# Adafruit_Trellis_4x4_3mm_HT16K33.net
KiCad netlist of a schematic drawn in Altium Designer
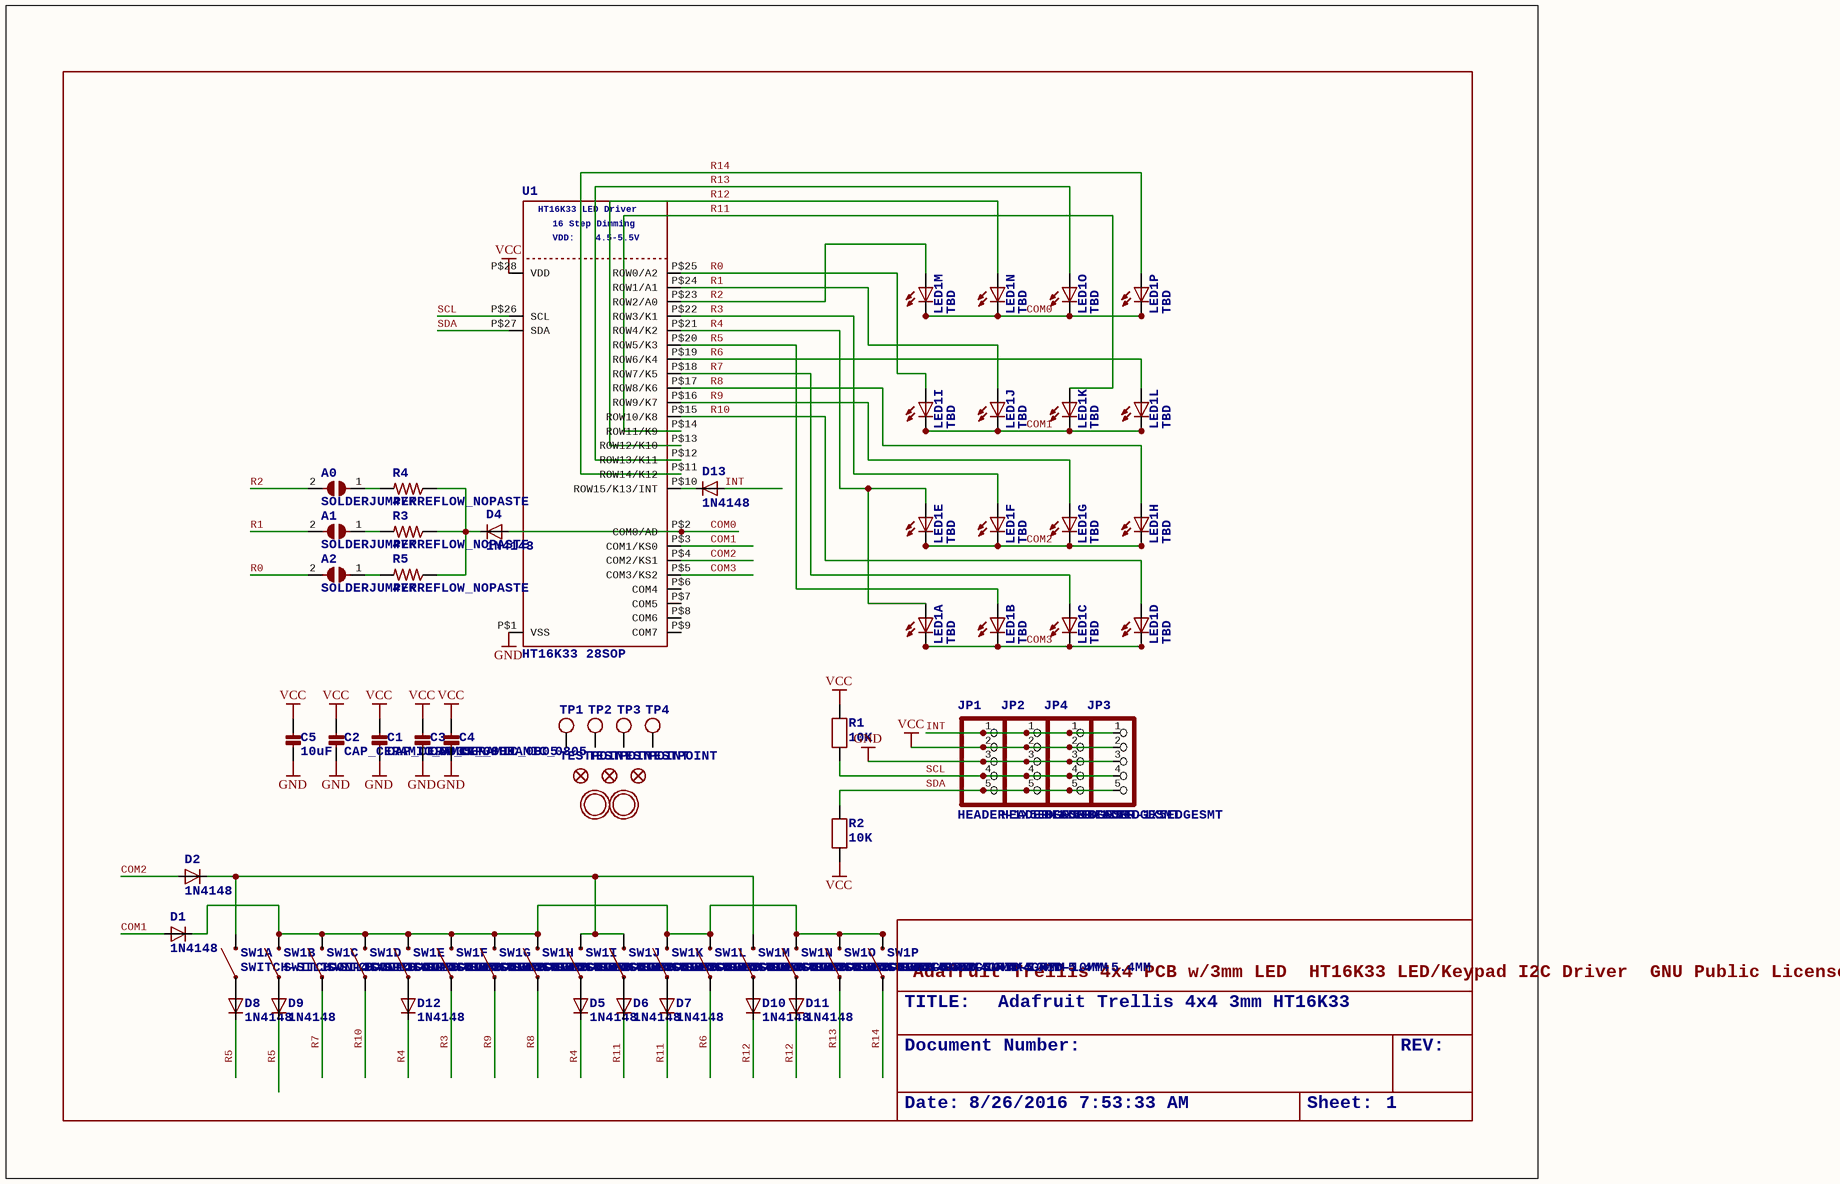
[diagram p0: Adafruit Trellis 4x4 3mm HT16K33.SchDoc]

(export (version "E")
  (design (tool "Eeschema 10.0.6"))
  (components
    (comp (ref "A0")
      (value "SOLDERJUMPERREFLOW_NOPASTE")
      (footprint "SOLDERJUMPER_REFLOW_NOPASTE")
      (libsource (lib "microbuilder") (part "SOLDERJUMPERREFLOW_NOPASTE"))
    )
    (comp (ref "A1")
      (value "SOLDERJUMPERREFLOW_NOPASTE")
      (footprint "SOLDERJUMPER_REFLOW_NOPASTE")
      (libsource (lib "microbuilder") (part "SOLDERJUMPERREFLOW_NOPASTE"))
    )
    (comp (ref "A2")
      (value "SOLDERJUMPERREFLOW_NOPASTE")
      (footprint "SOLDERJUMPER_REFLOW_NOPASTE")
      (libsource (lib "microbuilder") (part "SOLDERJUMPERREFLOW_NOPASTE"))
    )
    (comp (ref "C1")
      (value "CAP_CERAMIC_0805")
      (footprint "_0805")
      (libsource (lib "microbuilder") (part "CAP_CERAMIC_0805"))
    )
    (comp (ref "C2")
      (value "CAP_CERAMIC_0805")
      (footprint "_0805")
      (libsource (lib "microbuilder") (part "CAP_CERAMIC_0805"))
    )
    (comp (ref "C3")
      (value "CAP_CERAMIC_0805")
      (footprint "_0805")
      (libsource (lib "microbuilder") (part "CAP_CERAMIC_0805"))
    )
    (comp (ref "C4")
      (value "CAP_CERAMIC_0805")
      (footprint "_0805")
      (libsource (lib "microbuilder") (part "CAP_CERAMIC_0805"))
    )
    (comp (ref "C5")
      (value "10uF")
      (footprint "_0805")
      (libsource (lib "microbuilder") (part "CAP_CERAMIC_0805"))
    )
    (comp (ref "D1")
      (value "1N4148")
      (footprint "SOD-323")
      (libsource (lib "microbuilder") (part "DIODESOD-323"))
    )
    (comp (ref "D2")
      (value "1N4148")
      (footprint "SOD-323")
      (libsource (lib "microbuilder") (part "DIODESOD-323"))
    )
    (comp (ref "D4")
      (value "1N4148")
      (footprint "SOD-323F")
      (libsource (lib "adafruit") (part "DIODESOD-323F"))
    )
    (comp (ref "D5")
      (value "1N4148")
      (footprint "SOD-323")
      (libsource (lib "microbuilder") (part "DIODESOD-323"))
    )
    (comp (ref "D6")
      (value "1N4148")
      (footprint "SOD-323")
      (libsource (lib "microbuilder") (part "DIODESOD-323"))
    )
    (comp (ref "D7")
      (value "1N4148")
      (footprint "SOD-323")
      (libsource (lib "microbuilder") (part "DIODESOD-323"))
    )
    (comp (ref "D8")
      (value "1N4148")
      (footprint "SOD-323")
      (libsource (lib "microbuilder") (part "DIODESOD-323"))
    )
    (comp (ref "D9")
      (value "1N4148")
      (footprint "SOD-323")
      (libsource (lib "microbuilder") (part "DIODESOD-323"))
    )
    (comp (ref "D10")
      (value "1N4148")
      (footprint "SOD-323")
      (libsource (lib "microbuilder") (part "DIODESOD-323"))
    )
    (comp (ref "D11")
      (value "1N4148")
      (footprint "SOD-323")
      (libsource (lib "microbuilder") (part "DIODESOD-323"))
    )
    (comp (ref "D12")
      (value "1N4148")
      (footprint "SOD-323")
      (libsource (lib "microbuilder") (part "DIODESOD-323"))
    )
    (comp (ref "D13")
      (value "1N4148")
      (footprint "SOD-323")
      (libsource (lib "microbuilder") (part "DIODESOD-323"))
    )
    (comp (ref "FID1")
      (value "FIDUCIAL\"\"")
      (footprint "FIDUCIAL_1MM")
      (description "Fiducial Alignment Points   Various fiducial points for machine vision alignment.")
      (libsource (lib "microbuilder") (part "FIDUCIAL{dblquote}{dblquote}"))
    )
    (comp (ref "FID2")
      (value "FIDUCIAL\"\"")
      (footprint "FIDUCIAL_1MM")
      (description "Fiducial Alignment Points   Various fiducial points for machine vision alignment.")
      (libsource (lib "microbuilder") (part "FIDUCIAL{dblquote}{dblquote}"))
    )
    (comp (ref "FID3")
      (value "FIDUCIAL\"\"")
      (footprint "FIDUCIAL_1MM")
      (description "Fiducial Alignment Points   Various fiducial points for machine vision alignment.")
      (libsource (lib "microbuilder") (part "FIDUCIAL{dblquote}{dblquote}"))
    )
    (comp (ref "JP1")
      (value "HEADER-1X5EDGESMT")
      (footprint "1X5_SMT")
      (description "PIN HEADER")
      (libsource (lib "microbuilder") (part "HEADER-1X5EDGESMT"))
    )
    (comp (ref "JP2")
      (value "HEADER-1X5EDGESMT")
      (footprint "1X5_SMT")
      (description "PIN HEADER")
      (libsource (lib "microbuilder") (part "HEADER-1X5EDGESMT"))
    )
    (comp (ref "JP3")
      (value "HEADER-1X5EDGESMT")
      (footprint "1X5_SMT")
      (description "PIN HEADER")
      (libsource (lib "microbuilder") (part "HEADER-1X5EDGESMT"))
    )
    (comp (ref "JP4")
      (value "HEADER-1X5EDGESMT")
      (footprint "1X5_SMT")
      (description "PIN HEADER")
      (libsource (lib "microbuilder") (part "HEADER-1X5EDGESMT"))
    )
    (comp (ref "LED1")
      (value "TBD")
      (footprint "LED3MM-4X4GRID")
      (libsource (lib "microbuilder") (part "LED-3MM-4X4GRID-3MM"))
    )
    (comp (ref "R1")
      (value "10K")
      (footprint "_0805")
      (libsource (lib "microbuilder") (part "RESISTOR_0805"))
    )
    (comp (ref "R2")
      (value "10K")
      (footprint "_0805")
      (libsource (lib "microbuilder") (part "RESISTOR_0805"))
    )
    (comp (ref "R3")
      (value "47K")
      (footprint "R0805")
      (description "RESISTOR, American symbol")
      (libsource (lib "rcl") (part "R-US_R0805"))
    )
    (comp (ref "R4")
      (value "47K")
      (footprint "R0805")
      (description "RESISTOR, American symbol")
      (libsource (lib "rcl") (part "R-US_R0805"))
    )
    (comp (ref "R5")
      (value "47K")
      (footprint "R0805")
      (description "RESISTOR, American symbol")
      (libsource (lib "rcl") (part "R-US_R0805"))
    )
    (comp (ref "SW1")
      (value "SWITCH-SILICON-4X4GRID-10MM-5.4MM")
      (footprint "ELAST_PAD_SQUARE_10MM_5.4MM_4X4GRID")
      (libsource (lib "") (part "SWITCH-SILICON-4X4GRID-10MM-5.4MM_7"))
    )
    (comp (ref "TP1")
      (value "TESTPOINT")
      (footprint "TESTPOINT_SMT")
      (libsource (lib "microbuilder") (part "TESTPOINT"))
    )
    (comp (ref "TP2")
      (value "TESTPOINT")
      (footprint "TESTPOINT_SMT")
      (libsource (lib "microbuilder") (part "TESTPOINT"))
    )
    (comp (ref "TP3")
      (value "TESTPOINT")
      (footprint "TESTPOINT_SMT")
      (libsource (lib "microbuilder") (part "TESTPOINT"))
    )
    (comp (ref "TP4")
      (value "TESTPOINT")
      (footprint "TESTPOINT_SMT")
      (libsource (lib "microbuilder") (part "TESTPOINT"))
    )
    (comp (ref "U$1")
      (value "MOUNTINGHOLE2.5")
      (footprint "MOUNTINGHOLE_2.5_PLATED")
      (description "Mounting Hole   For #2 screws (0.086\"/2.18mm width, 0.094\"/2.4mm hole) use 2.5mm")
      (libsource (lib "microbuilder") (part "MOUNTINGHOLE2.5"))
    )
    (comp (ref "U$2")
      (value "MOUNTINGHOLE2.5")
      (footprint "MOUNTINGHOLE_2.5_PLATED")
      (description "Mounting Hole   For #2 screws (0.086\"/2.18mm width, 0.094\"/2.4mm hole) use 2.5mm")
      (libsource (lib "microbuilder") (part "MOUNTINGHOLE2.5"))
    )
    (comp (ref "U1")
      (value "HT16K33 28SOP")
      (footprint "SOP28_300MIL")
      (fields
        (field (name "HT16K33LEDDRIVER") "HT16K33 LED Driver")
        (field (name "VDD") "VDD:")
        (field (name "4.5-5.5V") "4.5-5.5V")
        (field (name "16STEPDIMMING") "16 Step Dimming")
      )
      (libsource (lib "microbuilder") (part "HT16K33_SOP28"))
    )
  )
  (nets
    (net (code "1") (name "/COM0") (class "Default")
      (node (ref "D4") (pin "A") (pinfunction "A_A") (pintype "passive"))
      (node (ref "LED1") (pin "K13") (pinfunction "C_K13") (pintype "passive"))
      (node (ref "LED1") (pin "K14") (pinfunction "C_K14") (pintype "passive"))
      (node (ref "LED1") (pin "K15") (pinfunction "C_K15") (pintype "passive"))
      (node (ref "LED1") (pin "K16") (pinfunction "C_K16") (pintype "passive"))
      (node (ref "U1") (pin "P$2") (pinfunction "COM0/AD_P$2") (pintype "passive"))
    )
    (net (code "2") (name "/COM1") (class "Default")
      (node (ref "D1") (pin "A") (pinfunction "A_A") (pintype "passive"))
      (node (ref "LED1") (pin "K10") (pinfunction "C_K10") (pintype "passive"))
      (node (ref "LED1") (pin "K11") (pinfunction "C_K11") (pintype "passive"))
      (node (ref "LED1") (pin "K12") (pinfunction "C_K12") (pintype "passive"))
      (node (ref "LED1") (pin "K9") (pinfunction "C_K9") (pintype "passive"))
      (node (ref "U1") (pin "P$3") (pinfunction "COM1/KS0_P$3") (pintype "passive"))
    )
    (net (code "3") (name "/COM2") (class "Default")
      (node (ref "D2") (pin "A") (pinfunction "A_A") (pintype "passive"))
      (node (ref "LED1") (pin "K5") (pinfunction "C_K5") (pintype "passive"))
      (node (ref "LED1") (pin "K6") (pinfunction "C_K6") (pintype "passive"))
      (node (ref "LED1") (pin "K7") (pinfunction "C_K7") (pintype "passive"))
      (node (ref "LED1") (pin "K8") (pinfunction "C_K8") (pintype "passive"))
      (node (ref "U1") (pin "P$4") (pinfunction "COM2/KS1_P$4") (pintype "passive"))
    )
    (net (code "4") (name "/COM3") (class "Default")
      (node (ref "LED1") (pin "K1") (pinfunction "C_K1") (pintype "passive"))
      (node (ref "LED1") (pin "K2") (pinfunction "C_K2") (pintype "passive"))
      (node (ref "LED1") (pin "K3") (pinfunction "C_K3") (pintype "passive"))
      (node (ref "LED1") (pin "K4") (pinfunction "C_K4") (pintype "passive"))
      (node (ref "U1") (pin "P$5") (pinfunction "COM3/KS2_P$5") (pintype "passive"))
    )
    (net (code "5") (name "/INT") (class "Default")
      (node (ref "D13") (pin "A") (pinfunction "A_A") (pintype "passive"))
      (node (ref "JP1") (pin "1") (pinfunction "1_1") (pintype "passive"))
      (node (ref "JP2") (pin "1") (pinfunction "1_1") (pintype "passive"))
      (node (ref "JP3") (pin "1") (pinfunction "1_1") (pintype "passive"))
      (node (ref "JP4") (pin "1") (pinfunction "1_1") (pintype "passive"))
    )
    (net (code "6") (name "/R0") (class "Default")
      (node (ref "A2") (pin "2") (pinfunction "2_2") (pintype "passive"))
      (node (ref "LED1") (pin "A9") (pinfunction "A_A9") (pintype "passive"))
      (node (ref "U1") (pin "P$25") (pinfunction "ROW0/A2_P$25") (pintype "passive"))
    )
    (net (code "7") (name "/R1") (class "Default")
      (node (ref "A1") (pin "2") (pinfunction "2_2") (pintype "passive"))
      (node (ref "LED1") (pin "A10") (pinfunction "A_A10") (pintype "passive"))
      (node (ref "U1") (pin "P$24") (pinfunction "ROW1/A1_P$24") (pintype "passive"))
    )
    (net (code "8") (name "/R2") (class "Default")
      (node (ref "A0") (pin "2") (pinfunction "2_2") (pintype "passive"))
      (node (ref "LED1") (pin "A13") (pinfunction "A_A13") (pintype "passive"))
      (node (ref "U1") (pin "P$23") (pinfunction "ROW2/A0_P$23") (pintype "passive"))
    )
    (net (code "9") (name "/R3") (class "Default")
      (node (ref "LED1") (pin "A6") (pinfunction "A_A6") (pintype "passive"))
      (node (ref "SW1") (pin "A6") (pinfunction "P$1_A6") (pintype "passive"))
      (node (ref "U1") (pin "P$22") (pinfunction "ROW3/K1_P$22") (pintype "passive"))
    )
    (net (code "10") (name "/R4") (class "Default")
      (node (ref "D12") (pin "C") (pinfunction "C_C") (pintype "passive"))
      (node (ref "D5") (pin "C") (pinfunction "C_C") (pintype "passive"))
      (node (ref "LED1") (pin "A1") (pinfunction "A_A1") (pintype "passive"))
      (node (ref "LED1") (pin "A5") (pinfunction "A_A5") (pintype "passive"))
      (node (ref "U1") (pin "P$21") (pinfunction "ROW4/K2_P$21") (pintype "passive"))
    )
    (net (code "11") (name "/R5") (class "Default")
      (node (ref "D8") (pin "C") (pinfunction "C_C") (pintype "passive"))
      (node (ref "D9") (pin "C") (pinfunction "C_C") (pintype "passive"))
      (node (ref "LED1") (pin "A2") (pinfunction "A_A2") (pintype "passive"))
      (node (ref "U1") (pin "P$20") (pinfunction "ROW5/K3_P$20") (pintype "passive"))
    )
    (net (code "12") (name "/R6") (class "Default")
      (node (ref "LED1") (pin "A12") (pinfunction "A_A12") (pintype "passive"))
      (node (ref "SW1") (pin "A12") (pinfunction "P$1_A12") (pintype "passive"))
      (node (ref "U1") (pin "P$19") (pinfunction "ROW6/K4_P$19") (pintype "passive"))
    )
    (net (code "13") (name "/R7") (class "Default")
      (node (ref "LED1") (pin "A3") (pinfunction "A_A3") (pintype "passive"))
      (node (ref "SW1") (pin "A3") (pinfunction "P$1_A3") (pintype "passive"))
      (node (ref "U1") (pin "P$18") (pinfunction "ROW7/K5_P$18") (pintype "passive"))
    )
    (net (code "14") (name "/R8") (class "Default")
      (node (ref "LED1") (pin "A8") (pinfunction "A_A8") (pintype "passive"))
      (node (ref "SW1") (pin "A8") (pinfunction "P$1_A8") (pintype "passive"))
      (node (ref "U1") (pin "P$17") (pinfunction "ROW8/K6_P$17") (pintype "passive"))
    )
    (net (code "15") (name "/R9") (class "Default")
      (node (ref "LED1") (pin "A7") (pinfunction "A_A7") (pintype "passive"))
      (node (ref "SW1") (pin "A7") (pinfunction "P$1_A7") (pintype "passive"))
      (node (ref "U1") (pin "P$16") (pinfunction "ROW9/K7_P$16") (pintype "passive"))
    )
    (net (code "16") (name "/R10") (class "Default")
      (node (ref "LED1") (pin "A4") (pinfunction "A_A4") (pintype "passive"))
      (node (ref "SW1") (pin "A4") (pinfunction "P$1_A4") (pintype "passive"))
      (node (ref "U1") (pin "P$15") (pinfunction "ROW10/K8_P$15") (pintype "passive"))
    )
    (net (code "17") (name "/R11") (class "Default")
      (node (ref "D6") (pin "C") (pinfunction "C_C") (pintype "passive"))
      (node (ref "D7") (pin "C") (pinfunction "C_C") (pintype "passive"))
      (node (ref "LED1") (pin "A11") (pinfunction "A_A11") (pintype "passive"))
      (node (ref "U1") (pin "P$14") (pinfunction "ROW11/K9_P$14") (pintype "passive"))
    )
    (net (code "18") (name "/R12") (class "Default")
      (node (ref "D10") (pin "C") (pinfunction "C_C") (pintype "passive"))
      (node (ref "D11") (pin "C") (pinfunction "C_C") (pintype "passive"))
      (node (ref "LED1") (pin "A14") (pinfunction "A_A14") (pintype "passive"))
      (node (ref "U1") (pin "P$13") (pinfunction "ROW12/K10_P$13") (pintype "passive"))
    )
    (net (code "19") (name "/R13") (class "Default")
      (node (ref "LED1") (pin "A15") (pinfunction "A_A15") (pintype "passive"))
      (node (ref "SW1") (pin "A15") (pinfunction "P$1_A15") (pintype "passive"))
      (node (ref "U1") (pin "P$12") (pinfunction "ROW13/K11_P$12") (pintype "passive"))
    )
    (net (code "20") (name "/R14") (class "Default")
      (node (ref "LED1") (pin "A16") (pinfunction "A_A16") (pintype "passive"))
      (node (ref "SW1") (pin "A16") (pinfunction "P$1_A16") (pintype "passive"))
      (node (ref "U1") (pin "P$11") (pinfunction "ROW14/K12_P$11") (pintype "passive"))
    )
    (net (code "21") (name "/SCL") (class "Default")
      (node (ref "JP1") (pin "4") (pinfunction "4_4") (pintype "passive"))
      (node (ref "JP2") (pin "4") (pinfunction "4_4") (pintype "passive"))
      (node (ref "JP3") (pin "4") (pinfunction "4_4") (pintype "passive"))
      (node (ref "JP4") (pin "4") (pinfunction "4_4") (pintype "passive"))
      (node (ref "R1") (pin "1") (pinfunction "1_1") (pintype "passive"))
      (node (ref "U1") (pin "P$26") (pinfunction "SCL_P$26") (pintype "passive"))
    )
    (net (code "22") (name "/SDA") (class "Default")
      (node (ref "JP1") (pin "5") (pinfunction "5_5") (pintype "passive"))
      (node (ref "JP2") (pin "5") (pinfunction "5_5") (pintype "passive"))
      (node (ref "JP3") (pin "5") (pinfunction "5_5") (pintype "passive"))
      (node (ref "JP4") (pin "5") (pinfunction "5_5") (pintype "passive"))
      (node (ref "R2") (pin "2") (pinfunction "2_2") (pintype "passive"))
      (node (ref "U1") (pin "P$27") (pinfunction "SDA_P$27") (pintype "passive"))
    )
    (net (code "23") (name "GND") (class "Default")
      (node (ref "C1") (pin "1") (pinfunction "1_1") (pintype "passive"))
      (node (ref "C2") (pin "1") (pinfunction "1_1") (pintype "passive"))
      (node (ref "C3") (pin "1") (pinfunction "1_1") (pintype "passive"))
      (node (ref "C4") (pin "1") (pinfunction "1_1") (pintype "passive"))
      (node (ref "C5") (pin "1") (pinfunction "1_1") (pintype "passive"))
      (node (ref "JP1") (pin "3") (pinfunction "3_3") (pintype "passive"))
      (node (ref "JP2") (pin "3") (pinfunction "3_3") (pintype "passive"))
      (node (ref "JP3") (pin "3") (pinfunction "3_3") (pintype "passive"))
      (node (ref "JP4") (pin "3") (pinfunction "3_3") (pintype "passive"))
      (node (ref "U1") (pin "P$1") (pinfunction "VSS_P$1") (pintype "passive"))
    )
    (net (code "24") (name "Net-(A0-Pad1)") (class "Default")
      (node (ref "A0") (pin "1") (pinfunction "1_1") (pintype "passive"))
      (node (ref "R4") (pin "2") (pinfunction "2_2") (pintype "passive"))
    )
    (net (code "25") (name "Net-(A1-Pad1)") (class "Default")
      (node (ref "A1") (pin "1") (pinfunction "1_1") (pintype "passive"))
      (node (ref "R3") (pin "2") (pinfunction "2_2") (pintype "passive"))
    )
    (net (code "26") (name "Net-(A2-Pad1)") (class "Default")
      (node (ref "A2") (pin "1") (pinfunction "1_1") (pintype "passive"))
      (node (ref "R5") (pin "2") (pinfunction "2_2") (pintype "passive"))
    )
    (net (code "27") (name "Net-(D4-PadC)") (class "Default")
      (node (ref "D4") (pin "C") (pinfunction "C_C") (pintype "passive"))
      (node (ref "R3") (pin "1") (pinfunction "1_1") (pintype "passive"))
      (node (ref "R4") (pin "1") (pinfunction "1_1") (pintype "passive"))
      (node (ref "R5") (pin "1") (pinfunction "1_1") (pintype "passive"))
    )
    (net (code "28") (name "Net-(SW1A-P$1)") (class "Default")
      (node (ref "D8") (pin "A") (pinfunction "A_A") (pintype "passive"))
      (node (ref "SW1") (pin "A1") (pinfunction "P$1_A1") (pintype "passive"))
    )
    (net (code "29") (name "Net-(SW1A-P$2)") (class "Default")
      (node (ref "D2") (pin "C") (pinfunction "C_C") (pintype "passive"))
      (node (ref "SW1") (pin "B1") (pinfunction "P$2_B1") (pintype "passive"))
      (node (ref "SW1") (pin "B10") (pinfunction "P$2_B10") (pintype "passive"))
      (node (ref "SW1") (pin "B13") (pinfunction "P$2_B13") (pintype "passive"))
      (node (ref "SW1") (pin "B9") (pinfunction "P$2_B9") (pintype "passive"))
    )
    (net (code "30") (name "Net-(SW1B-P$1)") (class "Default")
      (node (ref "D9") (pin "A") (pinfunction "A_A") (pintype "passive"))
      (node (ref "SW1") (pin "A2") (pinfunction "P$1_A2") (pintype "passive"))
    )
    (net (code "31") (name "Net-(SW1B-P$2)") (class "Default")
      (node (ref "D1") (pin "C") (pinfunction "C_C") (pintype "passive"))
      (node (ref "SW1") (pin "B11") (pinfunction "P$2_B11") (pintype "passive"))
      (node (ref "SW1") (pin "B12") (pinfunction "P$2_B12") (pintype "passive"))
      (node (ref "SW1") (pin "B14") (pinfunction "P$2_B14") (pintype "passive"))
      (node (ref "SW1") (pin "B15") (pinfunction "P$2_B15") (pintype "passive"))
      (node (ref "SW1") (pin "B16") (pinfunction "P$2_B16") (pintype "passive"))
      (node (ref "SW1") (pin "B2") (pinfunction "P$2_B2") (pintype "passive"))
      (node (ref "SW1") (pin "B3") (pinfunction "P$2_B3") (pintype "passive"))
      (node (ref "SW1") (pin "B4") (pinfunction "P$2_B4") (pintype "passive"))
      (node (ref "SW1") (pin "B5") (pinfunction "P$2_B5") (pintype "passive"))
      (node (ref "SW1") (pin "B6") (pinfunction "P$2_B6") (pintype "passive"))
      (node (ref "SW1") (pin "B7") (pinfunction "P$2_B7") (pintype "passive"))
      (node (ref "SW1") (pin "B8") (pinfunction "P$2_B8") (pintype "passive"))
    )
    (net (code "32") (name "Net-(SW1E-P$1)") (class "Default")
      (node (ref "D12") (pin "A") (pinfunction "A_A") (pintype "passive"))
      (node (ref "SW1") (pin "A5") (pinfunction "P$1_A5") (pintype "passive"))
    )
    (net (code "33") (name "Net-(SW1I-P$1)") (class "Default")
      (node (ref "D5") (pin "A") (pinfunction "A_A") (pintype "passive"))
      (node (ref "SW1") (pin "A9") (pinfunction "P$1_A9") (pintype "passive"))
    )
    (net (code "34") (name "Net-(SW1J-P$1)") (class "Default")
      (node (ref "D6") (pin "A") (pinfunction "A_A") (pintype "passive"))
      (node (ref "SW1") (pin "A10") (pinfunction "P$1_A10") (pintype "passive"))
    )
    (net (code "35") (name "Net-(SW1K-P$1)") (class "Default")
      (node (ref "D7") (pin "A") (pinfunction "A_A") (pintype "passive"))
      (node (ref "SW1") (pin "A11") (pinfunction "P$1_A11") (pintype "passive"))
    )
    (net (code "36") (name "Net-(SW1M-P$1)") (class "Default")
      (node (ref "D10") (pin "A") (pinfunction "A_A") (pintype "passive"))
      (node (ref "SW1") (pin "A13") (pinfunction "P$1_A13") (pintype "passive"))
    )
    (net (code "37") (name "Net-(SW1N-P$1)") (class "Default")
      (node (ref "D11") (pin "A") (pinfunction "A_A") (pintype "passive"))
      (node (ref "SW1") (pin "A14") (pinfunction "P$1_A14") (pintype "passive"))
    )
    (net (code "38") (name "Net-(U1-ROW15{slash}K13{slash}INT)") (class "Default")
      (node (ref "D13") (pin "C") (pinfunction "C_C") (pintype "passive"))
      (node (ref "U1") (pin "P$10") (pinfunction "ROW15/K13/INT_P$10") (pintype "passive"))
    )
    (net (code "39") (name "VCC") (class "Default")
      (node (ref "C1") (pin "2") (pinfunction "2_2") (pintype "passive"))
      (node (ref "C2") (pin "2") (pinfunction "2_2") (pintype "passive"))
      (node (ref "C3") (pin "2") (pinfunction "2_2") (pintype "passive"))
      (node (ref "C4") (pin "2") (pinfunction "2_2") (pintype "passive"))
      (node (ref "C5") (pin "2") (pinfunction "2_2") (pintype "passive"))
      (node (ref "JP1") (pin "2") (pinfunction "2_2") (pintype "passive"))
      (node (ref "JP2") (pin "2") (pinfunction "2_2") (pintype "passive"))
      (node (ref "JP3") (pin "2") (pinfunction "2_2") (pintype "passive"))
      (node (ref "JP4") (pin "2") (pinfunction "2_2") (pintype "passive"))
      (node (ref "R1") (pin "2") (pinfunction "2_2") (pintype "passive"))
      (node (ref "R2") (pin "1") (pinfunction "1_1") (pintype "passive"))
      (node (ref "U1") (pin "P$28") (pinfunction "VDD_P$28") (pintype "passive"))
    )
    (net (code "40") (name "unconnected-(TP1-PadP$1)") (class "Default")
      (node (ref "TP1") (pin "P$1") (pinfunction "P$1_P$1") (pintype "passive"))
    )
    (net (code "41") (name "unconnected-(TP2-PadP$1)") (class "Default")
      (node (ref "TP2") (pin "P$1") (pinfunction "P$1_P$1") (pintype "passive"))
    )
    (net (code "42") (name "unconnected-(TP3-PadP$1)") (class "Default")
      (node (ref "TP3") (pin "P$1") (pinfunction "P$1_P$1") (pintype "passive"))
    )
    (net (code "43") (name "unconnected-(TP4-PadP$1)") (class "Default")
      (node (ref "TP4") (pin "P$1") (pinfunction "P$1_P$1") (pintype "passive"))
    )
    (net (code "44") (name "unconnected-(U1-COM4-PadP$6)") (class "Default")
      (node (ref "U1") (pin "P$6") (pinfunction "COM4_P$6") (pintype "passive"))
    )
    (net (code "45") (name "unconnected-(U1-COM5-PadP$7)") (class "Default")
      (node (ref "U1") (pin "P$7") (pinfunction "COM5_P$7") (pintype "passive"))
    )
    (net (code "46") (name "unconnected-(U1-COM6-PadP$8)") (class "Default")
      (node (ref "U1") (pin "P$8") (pinfunction "COM6_P$8") (pintype "passive"))
    )
    (net (code "47") (name "unconnected-(U1-COM7-PadP$9)") (class "Default")
      (node (ref "U1") (pin "P$9") (pinfunction "COM7_P$9") (pintype "passive"))
    )
  )
)
